# power.net
KiCad netlist of a schematic drawn in Altium Designer
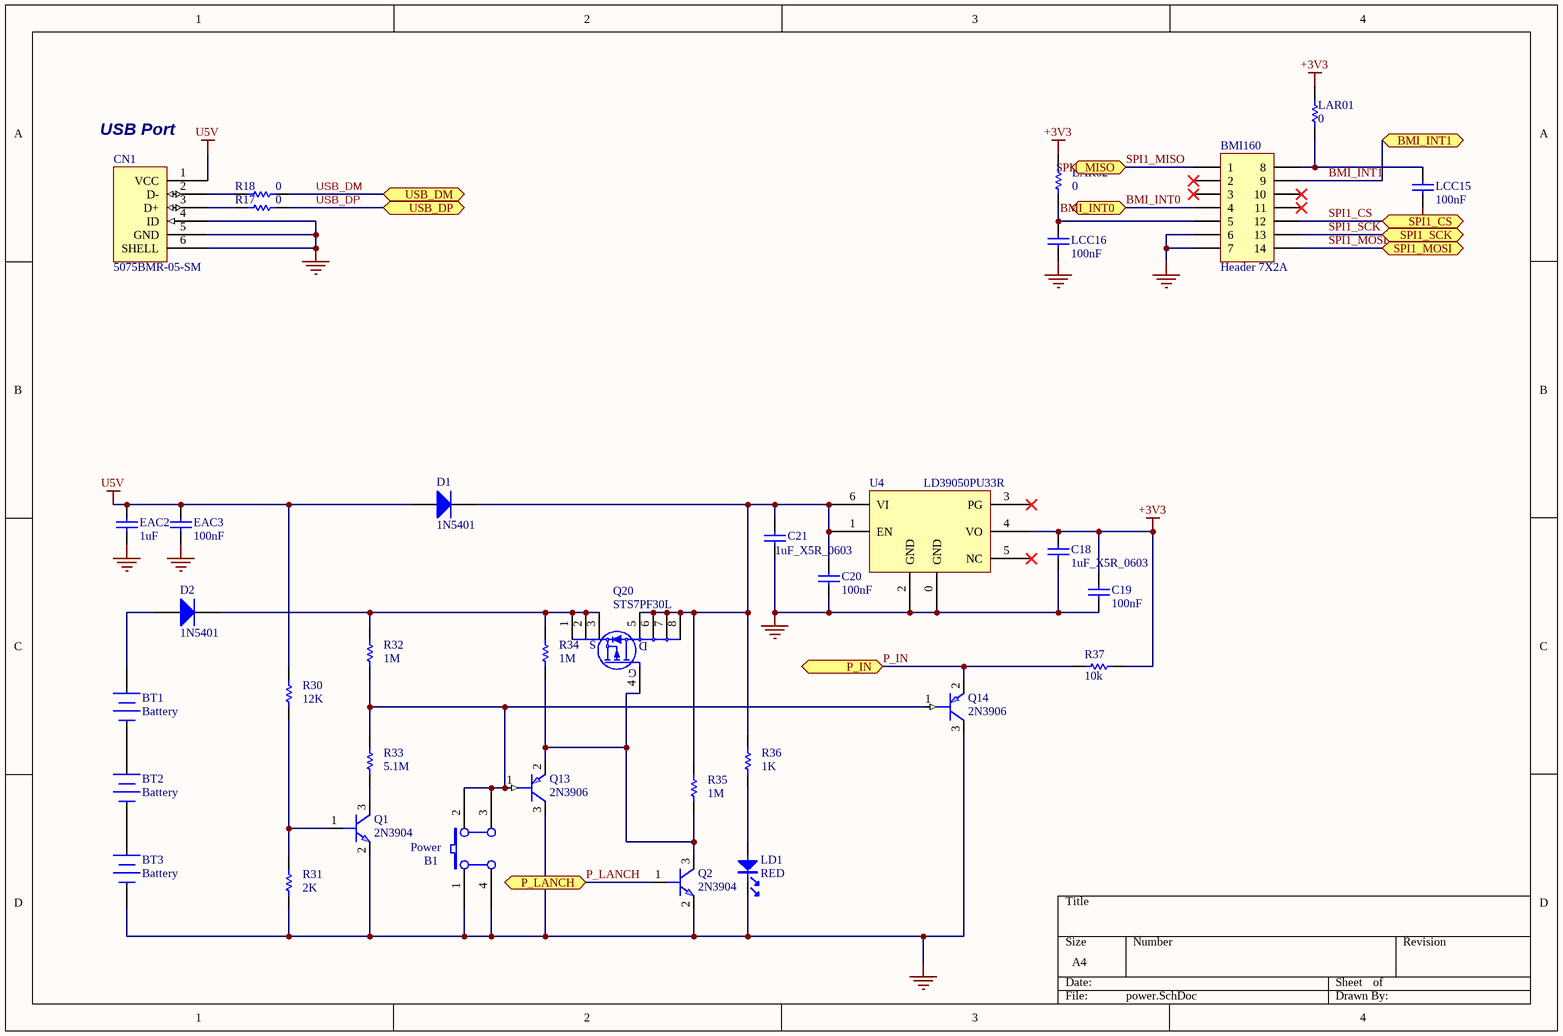
[diagram p0: power.SchDoc]

(export (version "E")
  (design (tool "Eeschema 10.0.6"))
  (components
    (comp (ref "B1")
      (value "Power")
      (footprint "PB10")
      (description "SE PUSHBUTTON")
      (libsource (lib "Documents") (part "SW PUSHBUTTON"))
    )
    (comp (ref "BMI160")
      (value "Header 7X2A")
      (footprint "BMI160")
      (description "Header, 7-Pin, Dual row")
      (fields (field (name "PUBLISHER") "Altium Limited"))
      (libsource (lib "Miscellaneous Connectors") (part "Header 7X2A"))
    )
    (comp (ref "BT1")
      (value "Battery")
      (footprint "BAT")
      (description "Multicell Battery")
      (fields (field (name "PUBLISHER") "Altium Limited"))
      (libsource (lib "Miscellaneous Devices") (part "Battery"))
    )
    (comp (ref "BT2")
      (value "Battery")
      (footprint "BAT")
      (description "Multicell Battery")
      (fields (field (name "PUBLISHER") "Altium Limited"))
      (libsource (lib "Miscellaneous Devices") (part "Battery"))
    )
    (comp (ref "BT3")
      (value "Battery")
      (footprint "BAT")
      (description "Multicell Battery")
      (fields (field (name "PUBLISHER") "Altium Limited"))
      (libsource (lib "Miscellaneous Devices") (part "Battery"))
    )
    (comp (ref "C18")
      (value "1uF_X5R_0603")
      (footprint "0603C")
      (description "0603  X5R 1礔")
      (fields (field (name "TOLERANCE") "10%"))
      (libsource (lib "MB963_1") (part "CAP SMD 0603  X5R 1礔 25V 10%"))
    )
    (comp (ref "C19")
      (value "100nF")
      (footprint "0603C")
      (description "Capacitor 0402 / 0603 / 0805")
      (libsource (lib "MCD_TOOLS") (part "Capacitor_ST"))
    )
    (comp (ref "C20")
      (value "100nF")
      (footprint "0603C")
      (description "Capacitor 0402 / 0603 / 0805")
      (libsource (lib "MCD_TOOLS") (part "Capacitor_ST"))
    )
    (comp (ref "C21")
      (value "1uF_X5R_0603")
      (footprint "0603C")
      (description "0603  X5R 1礔")
      (fields (field (name "TOLERANCE") "10%"))
      (libsource (lib "MB963_1") (part "CAP SMD 0603  X5R 1礔 25V 10%"))
    )
    (comp (ref "CN1")
      (value "5075BMR-05-SM")
      (footprint "USB-MINI-B-SMD")
      (description "USB-MINI-typeB connector")
      (libsource (lib "MCD_TOOLS") (part "USB-MINI-typeB connector"))
    )
    (comp (ref "D1")
      (value "1N5401")
      (footprint "SMA")
      (description "STPS2L30A")
      (libsource (lib "Nucleo_64") (part "STPS2L30A"))
    )
    (comp (ref "D2")
      (value "1N5401")
      (footprint "SMA")
      (description "STPS2L30A")
      (libsource (lib "Nucleo_64") (part "STPS2L30A"))
    )
    (comp (ref "EAC2")
      (value "1uF")
      (footprint "0603C")
      (description "Capacitor")
      (fields (field (name "PUBLISHER") "Altium Limited"))
      (libsource (lib "Miscellaneous Devices") (part "CAP"))
    )
    (comp (ref "EAC3")
      (value "100nF")
      (footprint "0603C")
      (description "Capacitor")
      (fields (field (name "PUBLISHER") "Altium Limited"))
      (libsource (lib "Miscellaneous Devices") (part "CAP"))
    )
    (comp (ref "LAR01")
      (value "0")
      (footprint "0603R")
      (description "Resistor")
      (fields (field (name "PUBLISHER") "Altium Limited"))
      (libsource (lib "Miscellaneous Devices") (part "res1"))
    )
    (comp (ref "LAR02")
      (value "0")
      (footprint "0603R")
      (description "Resistor")
      (fields (field (name "PUBLISHER") "Altium Limited"))
      (libsource (lib "Miscellaneous Devices") (part "res1"))
    )
    (comp (ref "LCC15")
      (value "100nF")
      (footprint "0603C")
      (description "Capacitor")
      (fields (field (name "PUBLISHER") "Altium Limited"))
      (libsource (lib "Miscellaneous Devices") (part "CAP"))
    )
    (comp (ref "LCC16")
      (value "100nF")
      (footprint "0603C")
      (description "Capacitor")
      (fields (field (name "PUBLISHER") "Altium Limited"))
      (libsource (lib "Miscellaneous Devices") (part "CAP"))
    )
    (comp (ref "LD1") (value "RED") (footprint "0603D") (libsource (lib "MB963_1") (part "PHOTO")))
    (comp (ref "Q1") (value "2N3904") (footprint "SOT-23") (libsource (lib "*") (part "2N5551")))
    (comp (ref "Q2") (value "2N3904") (footprint "SOT-23") (libsource (lib "*") (part "2N5551")))
    (comp (ref "Q13") (value "2N3906") (footprint "SOT-23") (libsource (lib "*") (part "2N5401")))
    (comp (ref "Q14") (value "2N3906") (footprint "SOT-23") (libsource (lib "*") (part "2N5401")))
    (comp (ref "Q20") (value "STS7PF30L") (footprint "SO8") (libsource (lib "Nucleo_64") (part "STS7PF30L")))
    (comp (ref "R17")
      (value "0")
      (footprint "0603R")
      (description "Resistor 0402 / 0603 / 0805")
      (libsource (lib "Miscellaneous Devices") (part "Res1"))
    )
    (comp (ref "R18")
      (value "0")
      (footprint "0603R")
      (description "Resistor 0402 / 0603 / 0805")
      (libsource (lib "Miscellaneous Devices") (part "Res1"))
    )
    (comp (ref "R30")
      (value "12K")
      (footprint "0603R")
      (description "Resistor 0402 / 0603 / 0805")
      (libsource (lib "MCD_TOOLS") (part "Resistor_ST"))
    )
    (comp (ref "R31")
      (value "2K")
      (footprint "0603R")
      (description "Resistor 0402 / 0603 / 0805")
      (libsource (lib "MCD_TOOLS") (part "Resistor_ST"))
    )
    (comp (ref "R32")
      (value "1M")
      (footprint "0603R")
      (description "Resistor 0402 / 0603 / 0805")
      (libsource (lib "MCD_TOOLS") (part "Resistor_ST"))
    )
    (comp (ref "R33")
      (value "5.1M")
      (footprint "0603R")
      (description "Resistor 0402 / 0603 / 0805")
      (libsource (lib "MCD_TOOLS") (part "Resistor_ST"))
    )
    (comp (ref "R34")
      (value "1M")
      (footprint "0603R")
      (description "Resistor 0402 / 0603 / 0805")
      (libsource (lib "MCD_TOOLS") (part "Resistor_ST"))
    )
    (comp (ref "R35")
      (value "1M")
      (footprint "0603R")
      (description "Resistor 0402 / 0603 / 0805")
      (libsource (lib "MCD_TOOLS") (part "Resistor_ST"))
    )
    (comp (ref "R36")
      (value "1K")
      (footprint "0603R")
      (description "Resistor 0402 / 0603 / 0805")
      (libsource (lib "MCD_TOOLS") (part "Resistor_ST"))
    )
    (comp (ref "R37")
      (value "10k")
      (footprint "0603R")
      (description "Resistor 0402 / 0603 / 0805")
      (libsource (lib "MCD_TOOLS") (part "Resistor_ST"))
    )
    (comp (ref "U4")
      (value "LD39050PU33R")
      (footprint "DFN6(3X3)")
      (libsource (lib "Nucleo_64") (part "LD39050P"))
    )
  )
  (nets
    (net (code "1") (name "+3V3") (class "Default")
      (node (ref "C18") (pin "1") (pinfunction "1_1") (pintype "passive"))
      (node (ref "C19") (pin "2") (pinfunction "2_2") (pintype "passive"))
      (node (ref "LAR01") (pin "2") (pinfunction "2_2") (pintype "passive"))
      (node (ref "LAR02") (pin "2") (pinfunction "2_2") (pintype "passive"))
      (node (ref "R37") (pin "1") (pinfunction "1_1") (pintype "passive"))
      (node (ref "U4") (pin "4") (pinfunction "VO_4") (pintype "passive"))
    )
    (net (code "2") (name "/BMI_INT0") (class "Default")
      (node (ref "BMI160") (pin "4") (pinfunction "4_4") (pintype "passive"))
    )
    (net (code "3") (name "/BMI_INT1") (class "Default")
      (node (ref "BMI160") (pin "9") (pinfunction "9_9") (pintype "passive"))
    )
    (net (code "4") (name "/P_IN") (class "Default")
      (node (ref "Q14") (pin "2") (pinfunction "EMITTER_2") (pintype "passive"))
      (node (ref "R37") (pin "2") (pinfunction "2_2") (pintype "passive"))
    )
    (net (code "5") (name "/P_LANCH") (class "Default")
      (node (ref "Q2") (pin "1") (pinfunction "B_1") (pintype "passive"))
    )
    (net (code "6") (name "/SPI1_CS") (class "Default")
      (node (ref "BMI160") (pin "12") (pinfunction "12_12") (pintype "passive"))
    )
    (net (code "7") (name "/SPI1_MISO") (class "Default")
      (node (ref "BMI160") (pin "1") (pinfunction "1_1") (pintype "passive"))
    )
    (net (code "8") (name "/SPI1_MOSI") (class "Default")
      (node (ref "BMI160") (pin "14") (pinfunction "14_14") (pintype "passive"))
    )
    (net (code "9") (name "/SPI1_SCK") (class "Default")
      (node (ref "BMI160") (pin "13") (pinfunction "13_13") (pintype "passive"))
    )
    (net (code "10") (name "/USB_DM") (class "Default")
      (node (ref "R18") (pin "2") (pinfunction "2_2") (pintype "passive"))
    )
    (net (code "11") (name "/USB_DP") (class "Default")
      (node (ref "R17") (pin "2") (pinfunction "2_2") (pintype "passive"))
    )
    (net (code "12") (name "GND") (class "Default")
      (node (ref "B1") (pin "1") (pinfunction "A0_1") (pintype "passive"))
      (node (ref "B1") (pin "4") (pinfunction "A1_4") (pintype "passive"))
      (node (ref "BMI160") (pin "6") (pinfunction "6_6") (pintype "passive"))
      (node (ref "BMI160") (pin "7") (pinfunction "7_7") (pintype "passive"))
      (node (ref "BT3") (pin "2") (pinfunction "-_2") (pintype "passive"))
      (node (ref "C18") (pin "2") (pinfunction "2_2") (pintype "passive"))
      (node (ref "C19") (pin "1") (pinfunction "1_1") (pintype "passive"))
      (node (ref "C20") (pin "1") (pinfunction "1_1") (pintype "passive"))
      (node (ref "C21") (pin "2") (pinfunction "2_2") (pintype "passive"))
      (node (ref "CN1") (pin "4") (pinfunction "ID_4") (pintype "input"))
      (node (ref "CN1") (pin "5") (pinfunction "GND_5") (pintype "power_in"))
      (node (ref "CN1") (pin "6") (pinfunction "SHELL_6") (pintype "power_in"))
      (node (ref "EAC2") (pin "2") (pinfunction "2_2") (pintype "passive"))
      (node (ref "EAC3") (pin "2") (pinfunction "2_2") (pintype "passive"))
      (node (ref "LCC15") (pin "1") (pinfunction "1_1") (pintype "passive"))
      (node (ref "LCC16") (pin "1") (pinfunction "1_1") (pintype "passive"))
      (node (ref "LD1") (pin "2") (pintype "passive"))
      (node (ref "Q1") (pin "2") (pinfunction "E_2") (pintype "passive"))
      (node (ref "Q13") (pin "3") (pinfunction "COLLECTOR_3") (pintype "passive"))
      (node (ref "Q14") (pin "3") (pinfunction "COLLECTOR_3") (pintype "passive"))
      (node (ref "Q2") (pin "2") (pinfunction "E_2") (pintype "passive"))
      (node (ref "R31") (pin "1") (pinfunction "1_1") (pintype "passive"))
      (node (ref "U4") (pin "0") (pinfunction "GND_0") (pintype "passive"))
      (node (ref "U4") (pin "2") (pinfunction "GND_2") (pintype "passive"))
    )
    (net (code "13") (name "Net-(B1-B0)") (class "Default")
      (node (ref "B1") (pin "2") (pinfunction "B0_2") (pintype "passive"))
      (node (ref "B1") (pin "3") (pinfunction "B1_3") (pintype "passive"))
      (node (ref "Q13") (pin "1") (pinfunction "BASE_1") (pintype "input"))
      (node (ref "Q14") (pin "1") (pinfunction "BASE_1") (pintype "input"))
      (node (ref "R32") (pin "1") (pinfunction "1_1") (pintype "passive"))
      (node (ref "R33") (pin "2") (pinfunction "2_2") (pintype "passive"))
    )
    (net (code "14") (name "Net-(BMI160-Pad5)") (class "Default")
      (node (ref "BMI160") (pin "5") (pinfunction "5_5") (pintype "passive"))
      (node (ref "LAR02") (pin "1") (pinfunction "1_1") (pintype "passive"))
      (node (ref "LCC16") (pin "2") (pinfunction "2_2") (pintype "passive"))
    )
    (net (code "15") (name "Net-(BMI160-Pad8)") (class "Default")
      (node (ref "BMI160") (pin "8") (pinfunction "8_8") (pintype "passive"))
      (node (ref "LAR01") (pin "1") (pinfunction "1_1") (pintype "passive"))
      (node (ref "LCC15") (pin "2") (pinfunction "2_2") (pintype "passive"))
    )
    (net (code "16") (name "Net-(BT1-+)") (class "Default")
      (node (ref "BT1") (pin "1") (pinfunction "+_1") (pintype "passive"))
      (node (ref "D2") (pin "1") (pinfunction "A_1") (pintype "passive"))
    )
    (net (code "17") (name "Net-(BT1--)") (class "Default")
      (node (ref "BT1") (pin "2") (pinfunction "-_2") (pintype "passive"))
      (node (ref "BT2") (pin "1") (pinfunction "+_1") (pintype "passive"))
    )
    (net (code "18") (name "Net-(BT2--)") (class "Default")
      (node (ref "BT2") (pin "2") (pinfunction "-_2") (pintype "passive"))
      (node (ref "BT3") (pin "1") (pinfunction "+_1") (pintype "passive"))
    )
    (net (code "19") (name "Net-(CN1-D+)") (class "Default")
      (node (ref "CN1") (pin "3") (pinfunction "D+_3") (pintype "bidirectional"))
      (node (ref "R17") (pin "1") (pinfunction "1_1") (pintype "passive"))
    )
    (net (code "20") (name "Net-(CN1-D-)") (class "Default")
      (node (ref "CN1") (pin "2") (pinfunction "D-_2") (pintype "bidirectional"))
      (node (ref "R18") (pin "1") (pinfunction "1_1") (pintype "passive"))
    )
    (net (code "21") (name "Net-(D1-K)") (class "Default")
      (node (ref "C20") (pin "2") (pinfunction "2_2") (pintype "passive"))
      (node (ref "C21") (pin "1") (pinfunction "1_1") (pintype "passive"))
      (node (ref "D1") (pin "2") (pinfunction "K_2") (pintype "passive"))
      (node (ref "Q20") (pin "5") (pinfunction "D_5") (pintype "passive"))
      (node (ref "Q20") (pin "6") (pinfunction "D_6") (pintype "passive"))
      (node (ref "Q20") (pin "7") (pinfunction "D_7") (pintype "passive"))
      (node (ref "Q20") (pin "8") (pinfunction "D_8") (pintype "passive"))
      (node (ref "R35") (pin "2") (pinfunction "2_2") (pintype "passive"))
      (node (ref "R36") (pin "2") (pinfunction "2_2") (pintype "passive"))
      (node (ref "U4") (pin "1") (pinfunction "EN_1") (pintype "passive"))
      (node (ref "U4") (pin "6") (pinfunction "VI_6") (pintype "passive"))
    )
    (net (code "22") (name "Net-(D2-K)") (class "Default")
      (node (ref "D2") (pin "2") (pinfunction "K_2") (pintype "passive"))
      (node (ref "Q20") (pin "1") (pinfunction "S_1") (pintype "passive"))
      (node (ref "Q20") (pin "2") (pinfunction "S_2") (pintype "passive"))
      (node (ref "Q20") (pin "3") (pinfunction "S_3") (pintype "passive"))
      (node (ref "R32") (pin "2") (pinfunction "2_2") (pintype "passive"))
      (node (ref "R34") (pin "2") (pinfunction "2_2") (pintype "passive"))
    )
    (net (code "23") (name "Net-(LD1-Pad1)") (class "Default")
      (node (ref "LD1") (pin "1") (pintype "passive"))
      (node (ref "R36") (pin "1") (pinfunction "1_1") (pintype "passive"))
    )
    (net (code "24") (name "Net-(Q1-B)") (class "Default")
      (node (ref "Q1") (pin "1") (pinfunction "B_1") (pintype "passive"))
      (node (ref "R30") (pin "1") (pinfunction "1_1") (pintype "passive"))
      (node (ref "R31") (pin "2") (pinfunction "2_2") (pintype "passive"))
    )
    (net (code "25") (name "Net-(Q1-C)") (class "Default")
      (node (ref "Q1") (pin "3") (pinfunction "C_3") (pintype "passive"))
      (node (ref "R33") (pin "1") (pinfunction "1_1") (pintype "passive"))
    )
    (net (code "26") (name "Net-(Q13-EMITTER)") (class "Default")
      (node (ref "Q13") (pin "2") (pinfunction "EMITTER_2") (pintype "passive"))
      (node (ref "Q2") (pin "3") (pinfunction "C_3") (pintype "passive"))
      (node (ref "Q20") (pin "4") (pinfunction "G_4") (pintype "passive"))
      (node (ref "R34") (pin "1") (pinfunction "1_1") (pintype "passive"))
      (node (ref "R35") (pin "1") (pinfunction "1_1") (pintype "passive"))
    )
    (net (code "27") (name "U5V") (class "Default")
      (node (ref "CN1") (pin "1") (pinfunction "VCC_1") (pintype "power_in"))
      (node (ref "D1") (pin "1") (pinfunction "A_1") (pintype "passive"))
      (node (ref "EAC2") (pin "1") (pinfunction "1_1") (pintype "passive"))
      (node (ref "EAC3") (pin "1") (pinfunction "1_1") (pintype "passive"))
      (node (ref "R30") (pin "2") (pinfunction "2_2") (pintype "passive"))
    )
    (net (code "28") (name "unconnected-(BMI160-Pad2)") (class "Default")
      (node (ref "BMI160") (pin "2") (pinfunction "2_2") (pintype "passive+no_connect"))
    )
    (net (code "29") (name "unconnected-(BMI160-Pad3)") (class "Default")
      (node (ref "BMI160") (pin "3") (pinfunction "3_3") (pintype "passive+no_connect"))
    )
    (net (code "30") (name "unconnected-(BMI160-Pad10)") (class "Default")
      (node (ref "BMI160") (pin "10") (pinfunction "10_10") (pintype "passive+no_connect"))
    )
    (net (code "31") (name "unconnected-(BMI160-Pad11)") (class "Default")
      (node (ref "BMI160") (pin "11") (pinfunction "11_11") (pintype "passive+no_connect"))
    )
    (net (code "32") (name "unconnected-(U4-NC-Pad5)") (class "Default")
      (node (ref "U4") (pin "5") (pinfunction "NC_5") (pintype "passive+no_connect"))
    )
    (net (code "33") (name "unconnected-(U4-PG-Pad3)") (class "Default")
      (node (ref "U4") (pin "3") (pinfunction "PG_3") (pintype "passive+no_connect"))
    )
  )
)
